# SNES_RGBAmp.net
KiCad netlist of a schematic drawn in EAGLE
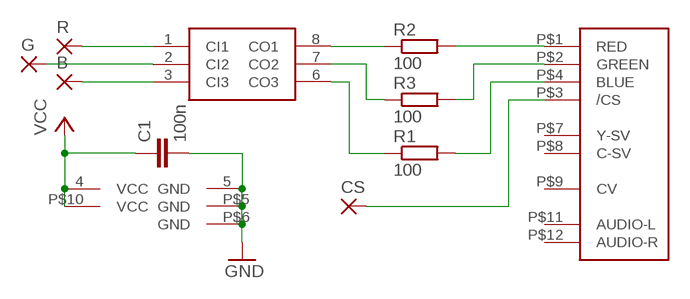
[diagram p0: schematic, sheet 1]

(export (version "E")
  (design (tool "Eeschema 10.0.6"))
  (components
    (comp (ref "B")
      (value "SMD2")
      (footprint "eagle-import:SMD1,27-2,54")
      (libsource (lib "eagle-import") (part "SMD2"))
    )
    (comp (ref "C1")
      (value "100n")
      (footprint "eagle-import:Z0805")
      (libsource (lib "eagle-import") (part "C0805"))
    )
    (comp (ref "CS")
      (value "SMD2")
      (footprint "eagle-import:SMD1,27-2,54")
      (libsource (lib "eagle-import") (part "SMD2"))
    )
    (comp (ref "G")
      (value "SMD2")
      (footprint "eagle-import:SMD1,27-2,54")
      (libsource (lib "eagle-import") (part "SMD2"))
    )
    (comp (ref "R")
      (value "SMD2")
      (footprint "eagle-import:SMD1,27-2,54")
      (libsource (lib "eagle-import") (part "SMD2"))
    )
    (comp (ref "R1")
      (value "100")
      (footprint "eagle-import:Z0805")
      (libsource (lib "eagle-import") (part "R0805"))
    )
    (comp (ref "R2")
      (value "100")
      (footprint "eagle-import:Z0805")
      (libsource (lib "eagle-import") (part "R0805"))
    )
    (comp (ref "R3")
      (value "100")
      (footprint "eagle-import:Z0805")
      (libsource (lib "eagle-import") (part "R0805"))
    )
    (comp (ref "U$1")
      (value "THS7314")
      (footprint "eagle-import:THS7314")
      (libsource (lib "eagle-import") (part "THS7314"))
    )
    (comp (ref "U$2")
      (value "SNES_MULTIAV")
      (footprint "eagle-import:SNES_MULTIAV")
      (libsource (lib "eagle-import") (part "SNES_MULTIAV"))
    )
  )
  (nets
    (net (code "1") (name "GND") (class "Default")
      (node (ref "C1") (pin "2") (pinfunction "2_2") (pintype "passive"))
      (node (ref "U$1") (pin "5") (pinfunction "GND_5") (pintype "bidirectional"))
      (node (ref "U$2") (pin "P$5") (pinfunction "GND_P$5") (pintype "bidirectional"))
      (node (ref "U$2") (pin "P$6") (pinfunction "GND_P$6") (pintype "bidirectional"))
    )
    (net (code "2") (name "Net-(B-P)") (class "Default")
      (node (ref "B") (pin "1") (pinfunction "P_1") (pintype "passive"))
      (node (ref "U$1") (pin "3") (pinfunction "CI3_3") (pintype "bidirectional"))
    )
    (net (code "3") (name "Net-(CS-P)") (class "Default")
      (node (ref "CS") (pin "1") (pinfunction "P_1") (pintype "passive"))
      (node (ref "U$2") (pin "P$3") (pinfunction "/CS_P$3") (pintype "bidirectional"))
    )
    (net (code "4") (name "Net-(G-P)") (class "Default")
      (node (ref "G") (pin "1") (pinfunction "P_1") (pintype "passive"))
      (node (ref "U$1") (pin "2") (pinfunction "CI2_2") (pintype "bidirectional"))
    )
    (net (code "5") (name "Net-(R-P)") (class "Default")
      (node (ref "R") (pin "1") (pinfunction "P_1") (pintype "passive"))
      (node (ref "U$1") (pin "1") (pinfunction "CI1_1") (pintype "bidirectional"))
    )
    (net (code "6") (name "Net-(U$1A-CO1)") (class "Default")
      (node (ref "R2") (pin "1") (pinfunction "1_1") (pintype "passive"))
      (node (ref "U$1") (pin "8") (pinfunction "CO1_8") (pintype "bidirectional"))
    )
    (net (code "7") (name "Net-(U$1A-CO2)") (class "Default")
      (node (ref "R3") (pin "1") (pinfunction "1_1") (pintype "passive"))
      (node (ref "U$1") (pin "7") (pinfunction "CO2_7") (pintype "bidirectional"))
    )
    (net (code "8") (name "Net-(U$1A-CO3)") (class "Default")
      (node (ref "R1") (pin "1") (pinfunction "1_1") (pintype "passive"))
      (node (ref "U$1") (pin "6") (pinfunction "CO3_6") (pintype "bidirectional"))
    )
    (net (code "9") (name "Net-(U$2A-BLUE)") (class "Default")
      (node (ref "R1") (pin "2") (pinfunction "2_2") (pintype "passive"))
      (node (ref "U$2") (pin "P$4") (pinfunction "BLUE_P$4") (pintype "bidirectional"))
    )
    (net (code "10") (name "Net-(U$2A-GREEN)") (class "Default")
      (node (ref "R3") (pin "2") (pinfunction "2_2") (pintype "passive"))
      (node (ref "U$2") (pin "P$2") (pinfunction "GREEN_P$2") (pintype "bidirectional"))
    )
    (net (code "11") (name "Net-(U$2A-RED)") (class "Default")
      (node (ref "R2") (pin "2") (pinfunction "2_2") (pintype "passive"))
      (node (ref "U$2") (pin "P$1") (pinfunction "RED_P$1") (pintype "bidirectional"))
    )
    (net (code "12") (name "VCC") (class "Default")
      (node (ref "C1") (pin "1") (pinfunction "1_1") (pintype "passive"))
      (node (ref "U$1") (pin "4") (pinfunction "VCC_4") (pintype "bidirectional"))
      (node (ref "U$2") (pin "P$10") (pinfunction "VCC_P$10") (pintype "bidirectional"))
    )
    (net (code "13") (name "unconnected-(U$2A-AUDIO-L-PadP$11)") (class "Default")
      (node (ref "U$2") (pin "P$11") (pinfunction "AUDIO-L_P$11") (pintype "bidirectional"))
    )
    (net (code "14") (name "unconnected-(U$2A-AUDIO-R-PadP$12)") (class "Default")
      (node (ref "U$2") (pin "P$12") (pinfunction "AUDIO-R_P$12") (pintype "bidirectional"))
    )
    (net (code "15") (name "unconnected-(U$2A-C-SV-PadP$8)") (class "Default")
      (node (ref "U$2") (pin "P$8") (pinfunction "C-SV_P$8") (pintype "bidirectional"))
    )
    (net (code "16") (name "unconnected-(U$2A-CV-PadP$9)") (class "Default")
      (node (ref "U$2") (pin "P$9") (pinfunction "CV_P$9") (pintype "bidirectional"))
    )
    (net (code "17") (name "unconnected-(U$2A-Y-SV-PadP$7)") (class "Default")
      (node (ref "U$2") (pin "P$7") (pinfunction "Y-SV_P$7") (pintype "bidirectional"))
    )
  )
)
